# Omega2-IO-Power.net
KiCad netlist of a schematic drawn in EAGLE
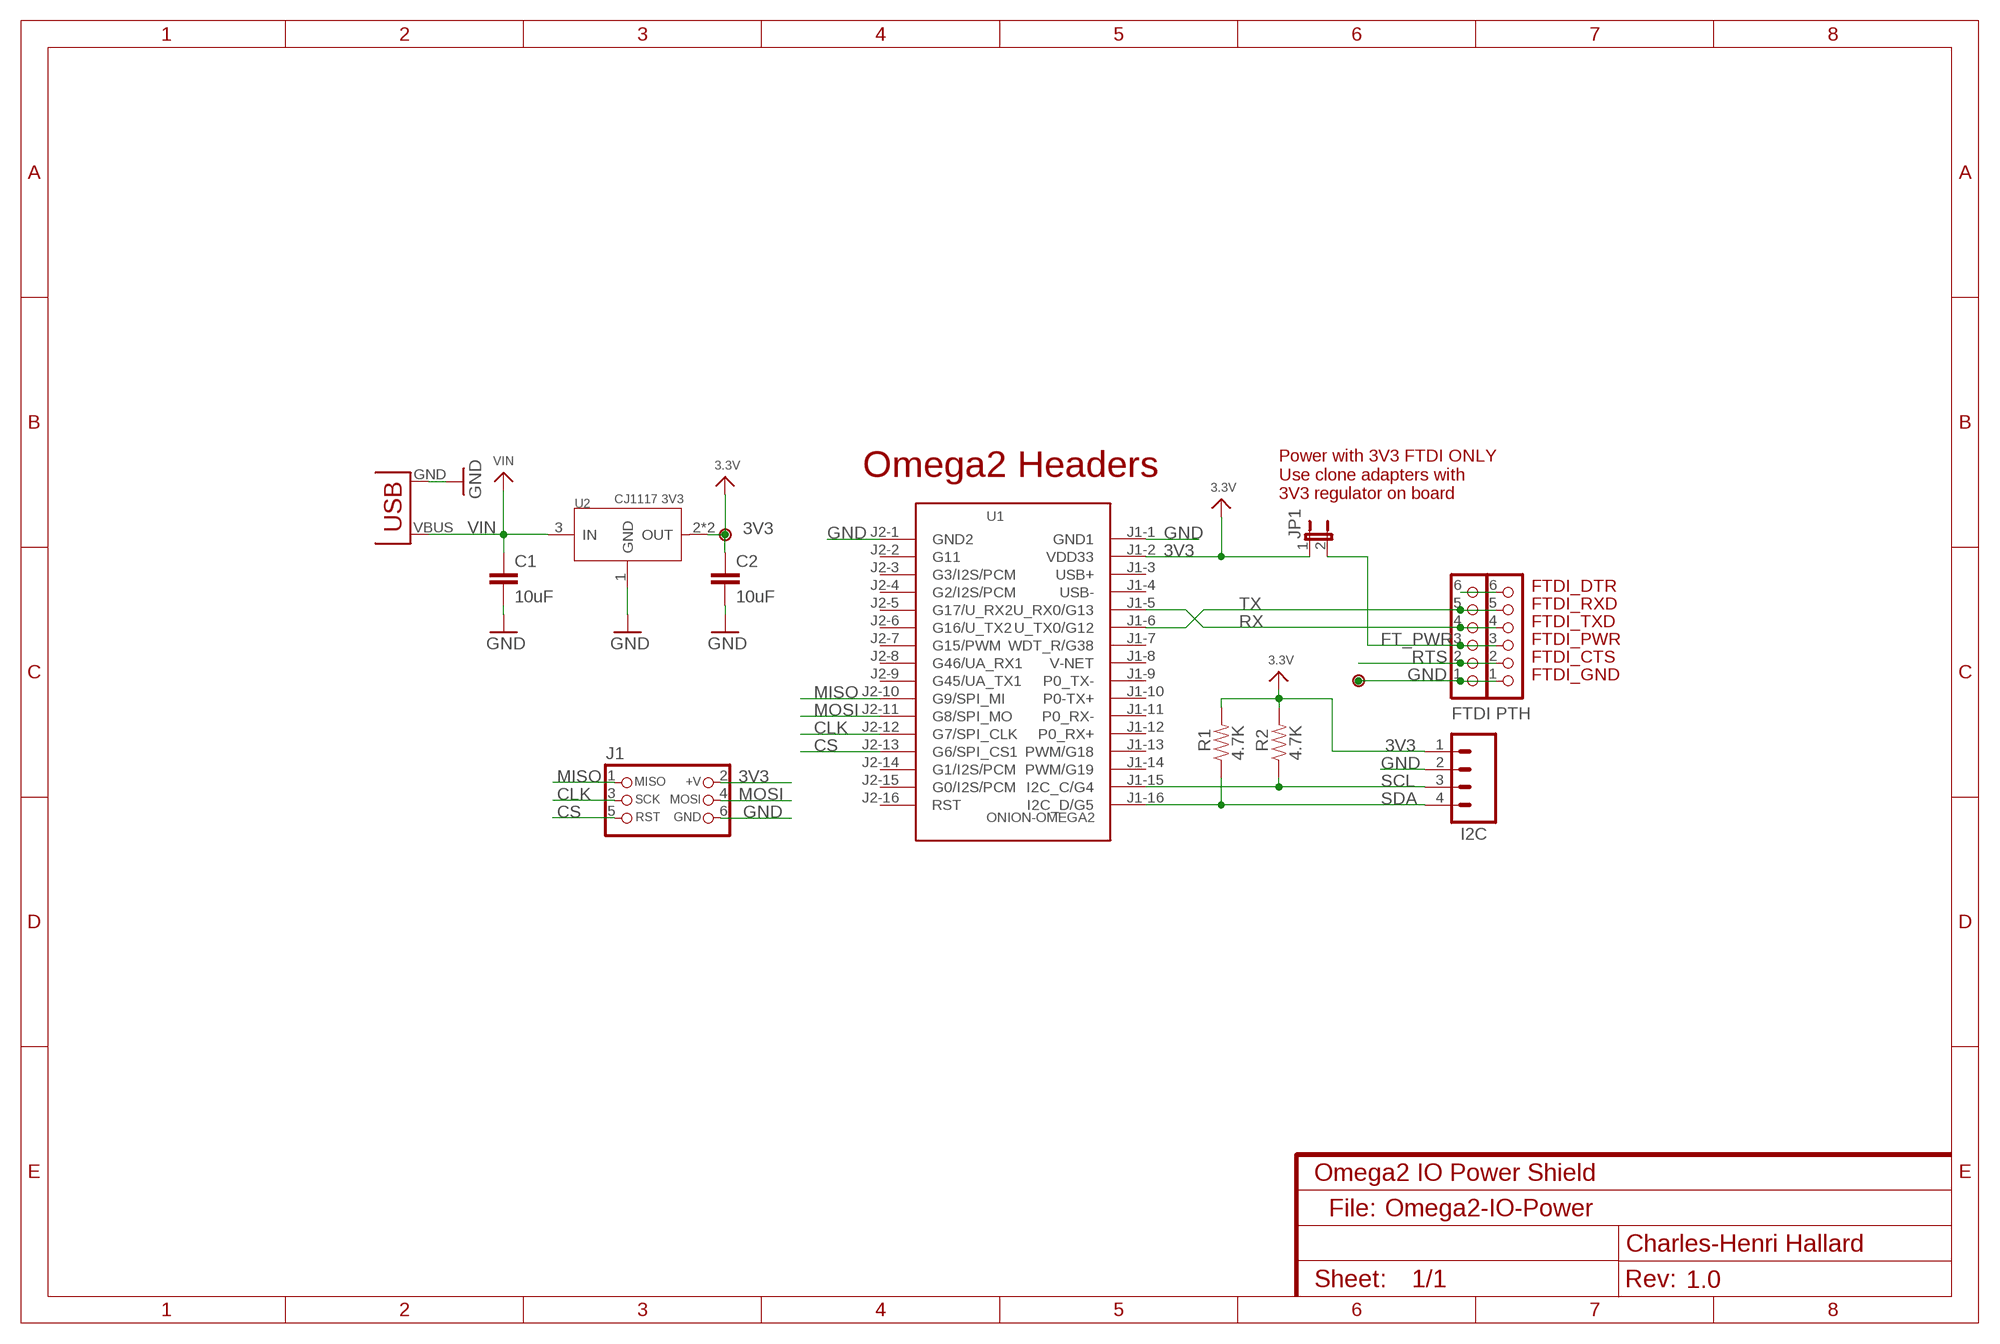
[diagram p0: schematic, sheet 1]

(export (version "E")
  (design (tool "Eeschema 10.0.6"))
  (components
    (comp (ref "C1")
      (value "10uF")
      (footprint "eagle-import:0805-CAP-LARGEPADS")
      (libsource (lib "eagle-import") (part "CAP0805-CAP-LARGEPADS"))
    )
    (comp (ref "C2")
      (value "10uF")
      (footprint "eagle-import:0805-CAP-LARGEPADS")
      (libsource (lib "eagle-import") (part "CAP0805-CAP-LARGEPADS"))
    )
    (comp (ref "FTDI")
      (value "CON_HEADER_1X06-PTH")
      (footprint "eagle-import:M1X6")
      (libsource (lib "eagle-import") (part "CON_HEADER_1X06-PTH"))
    )
    (comp (ref "I2C")
      (value "M04PTH")
      (footprint "eagle-import:1X04")
      (libsource (lib "eagle-import") (part "M04PTH"))
    )
    (comp (ref "J1")
      (value "CON_HEADER_PRG_AVR_ICSP-PTH")
      (footprint "eagle-import:HEADER_PRG_2X03")
      (libsource (lib "eagle-import") (part "CON_HEADER_PRG_AVR_ICSP-PTH"))
    )
    (comp (ref "JP1")
      (value "JUMPER2")
      (footprint "eagle-import:JUMPER2")
      (libsource (lib "eagle-import") (part "JUMPER2"))
    )
    (comp (ref "P1")
      (value "PADNORMAL")
      (footprint "eagle-import:PAD")
      (libsource (lib "eagle-import") (part "PADNORMAL"))
    )
    (comp (ref "P2")
      (value "PADNORMAL")
      (footprint "eagle-import:PAD")
      (libsource (lib "eagle-import") (part "PADNORMAL"))
    )
    (comp (ref "PTH")
      (value "CON_HEADER_1X06")
      (footprint "eagle-import:M1X6_MALE_RIGHT_ANGLED_SMD_NO_HOLES")
      (libsource (lib "eagle-import") (part "CON_HEADER_1X06"))
    )
    (comp (ref "R1")
      (value "4.7K")
      (footprint "eagle-import:0805-RES")
      (libsource (lib "eagle-import") (part "RESISTOR0805-RES"))
    )
    (comp (ref "R2")
      (value "4.7K")
      (footprint "eagle-import:0805-RES")
      (libsource (lib "eagle-import") (part "RESISTOR0805-RES"))
    )
    (comp (ref "U1")
      (value "ONION-OMEGA2")
      (footprint "eagle-import:ONION-2MM-2X16")
      (libsource (lib "eagle-import") (part "ONION-OMEGA2"))
    )
    (comp (ref "U2")
      (value "CJ1117 3V3")
      (footprint "eagle-import:SOT89")
      (libsource (lib "eagle-import") (part "CJ1117-3.3-1310120P1"))
    )
    (comp (ref "USB")
      (value "USB_POWER")
      (footprint "eagle-import:USB_MINIB_POWER")
      (libsource (lib "eagle-import") (part "USB_POWER"))
    )
  )
  (nets
    (net (code "1") (name "/CLK") (class "Default")
      (node (ref "J1") (pin "3") (pinfunction "SCK_3") (pintype "passive"))
      (node (ref "U1") (pin "J2-12") (pinfunction "G7/SPI_CLK_J2-12") (pintype "bidirectional"))
    )
    (net (code "2") (name "/CS") (class "Default")
      (node (ref "J1") (pin "5") (pinfunction "RST_5") (pintype "passive"))
      (node (ref "U1") (pin "J2-13") (pinfunction "G6/SPI_CS1_J2-13") (pintype "bidirectional"))
    )
    (net (code "3") (name "/FT_PWR") (class "Default")
      (node (ref "FTDI") (pin "3") (pinfunction "3_3") (pintype "passive"))
      (node (ref "JP1") (pin "2") (pinfunction "2_2") (pintype "passive"))
      (node (ref "PTH") (pin "3") (pinfunction "3_3") (pintype "passive"))
    )
    (net (code "4") (name "/MISO") (class "Default")
      (node (ref "J1") (pin "1") (pinfunction "MISO_1") (pintype "passive"))
      (node (ref "U1") (pin "J2-10") (pinfunction "G9/SPI_MI_J2-10") (pintype "bidirectional"))
    )
    (net (code "5") (name "/MOSI") (class "Default")
      (node (ref "J1") (pin "4") (pinfunction "MOSI_4") (pintype "passive"))
      (node (ref "U1") (pin "J2-11") (pinfunction "G8/SPI_MO_J2-11") (pintype "bidirectional"))
    )
    (net (code "6") (name "/RTS") (class "Default")
      (node (ref "FTDI") (pin "2") (pinfunction "2_2") (pintype "bidirectional"))
      (node (ref "PTH") (pin "2") (pinfunction "2_2") (pintype "bidirectional"))
    )
    (net (code "7") (name "/RX") (class "Default")
      (node (ref "FTDI") (pin "4") (pinfunction "4_4") (pintype "passive"))
      (node (ref "PTH") (pin "4") (pinfunction "4_4") (pintype "passive"))
      (node (ref "U1") (pin "J1-5") (pinfunction "U_RX0/G13_J1-5") (pintype "bidirectional"))
    )
    (net (code "8") (name "/SCL") (class "Default")
      (node (ref "I2C") (pin "3") (pinfunction "3_3") (pintype "passive"))
      (node (ref "R2") (pin "1") (pinfunction "1_1") (pintype "passive"))
      (node (ref "U1") (pin "J1-15") (pinfunction "I2C_C/G4_J1-15") (pintype "bidirectional"))
    )
    (net (code "9") (name "/SDA") (class "Default")
      (node (ref "I2C") (pin "4") (pinfunction "4_4") (pintype "passive"))
      (node (ref "R1") (pin "1") (pinfunction "1_1") (pintype "passive"))
      (node (ref "U1") (pin "J1-16") (pinfunction "I2C_D/G5_J1-16") (pintype "bidirectional"))
    )
    (net (code "10") (name "/TX") (class "Default")
      (node (ref "FTDI") (pin "5") (pinfunction "5_5") (pintype "passive"))
      (node (ref "PTH") (pin "5") (pinfunction "5_5") (pintype "passive"))
      (node (ref "U1") (pin "J1-6") (pinfunction "U_TX0/G12_J1-6") (pintype "bidirectional"))
    )
    (net (code "11") (name "3.3V") (class "Default")
      (node (ref "C2") (pin "1") (pinfunction "1_1") (pintype "passive"))
      (node (ref "I2C") (pin "1") (pinfunction "1_1") (pintype "passive"))
      (node (ref "J1") (pin "2") (pinfunction "+V_2") (pintype "passive"))
      (node (ref "JP1") (pin "1") (pinfunction "1_1") (pintype "passive"))
      (node (ref "P1") (pin "1") (pinfunction "1_1") (pintype "bidirectional"))
      (node (ref "R1") (pin "2") (pinfunction "2_2") (pintype "passive"))
      (node (ref "R2") (pin "2") (pinfunction "2_2") (pintype "passive"))
      (node (ref "U1") (pin "J1-2") (pinfunction "VDD33_J1-2") (pintype "bidirectional"))
      (node (ref "U2") (pin "2") (pinfunction "OUT_2") (pintype "bidirectional"))
      (node (ref "U2") (pin "4") (pinfunction "OUT_4") (pintype "bidirectional"))
    )
    (net (code "12") (name "GND") (class "Default")
      (node (ref "C1") (pin "2") (pinfunction "2_2") (pintype "passive"))
      (node (ref "C2") (pin "2") (pinfunction "2_2") (pintype "passive"))
      (node (ref "FTDI") (pin "1") (pinfunction "1_1") (pintype "bidirectional"))
      (node (ref "I2C") (pin "2") (pinfunction "2_2") (pintype "passive"))
      (node (ref "J1") (pin "6") (pinfunction "GND_6") (pintype "passive"))
      (node (ref "P2") (pin "1") (pinfunction "1_1") (pintype "bidirectional"))
      (node (ref "PTH") (pin "1") (pinfunction "1_1") (pintype "bidirectional"))
      (node (ref "U1") (pin "J1-1") (pinfunction "GND1_J1-1") (pintype "bidirectional"))
      (node (ref "U1") (pin "J2-1") (pinfunction "GND2_J2-1") (pintype "bidirectional"))
      (node (ref "U2") (pin "1") (pinfunction "GND_1") (pintype "bidirectional"))
      (node (ref "USB") (pin "GND") (pinfunction "GND_GND") (pintype "bidirectional"))
    )
    (net (code "13") (name "Net-(FTDI-Pad6)") (class "Default")
      (node (ref "FTDI") (pin "6") (pinfunction "6_6") (pintype "passive"))
      (node (ref "PTH") (pin "6") (pinfunction "6_6") (pintype "passive"))
    )
    (net (code "14") (name "VIN") (class "Default")
      (node (ref "C1") (pin "1") (pinfunction "1_1") (pintype "passive"))
      (node (ref "U2") (pin "3") (pinfunction "IN_3") (pintype "bidirectional"))
      (node (ref "USB") (pin "VBUS") (pinfunction "VCC_VBUS") (pintype "bidirectional"))
    )
    (net (code "15") (name "unconnected-(U1-G0{slash}I2S{slash}PCM-PadJ2-15)") (class "Default")
      (node (ref "U1") (pin "J2-15") (pinfunction "G0/I2S/PCM_J2-15") (pintype "bidirectional"))
    )
    (net (code "16") (name "unconnected-(U1-G1{slash}I2S{slash}PCM-PadJ2-14)") (class "Default")
      (node (ref "U1") (pin "J2-14") (pinfunction "G1/I2S/PCM_J2-14") (pintype "bidirectional"))
    )
    (net (code "17") (name "unconnected-(U1-G2{slash}I2S{slash}PCM-PadJ2-4)") (class "Default")
      (node (ref "U1") (pin "J2-4") (pinfunction "G2/I2S/PCM_J2-4") (pintype "bidirectional"))
    )
    (net (code "18") (name "unconnected-(U1-G3{slash}I2S{slash}PCM-PadJ2-3)") (class "Default")
      (node (ref "U1") (pin "J2-3") (pinfunction "G3/I2S/PCM_J2-3") (pintype "bidirectional"))
    )
    (net (code "19") (name "unconnected-(U1-G11-PadJ2-2)") (class "Default")
      (node (ref "U1") (pin "J2-2") (pinfunction "G11_J2-2") (pintype "bidirectional"))
    )
    (net (code "20") (name "unconnected-(U1-G15{slash}PWM-PadJ2-7)") (class "Default")
      (node (ref "U1") (pin "J2-7") (pinfunction "G15/PWM_J2-7") (pintype "bidirectional"))
    )
    (net (code "21") (name "unconnected-(U1-G16{slash}U_TX2-PadJ2-6)") (class "Default")
      (node (ref "U1") (pin "J2-6") (pinfunction "G16/U_TX2_J2-6") (pintype "bidirectional"))
    )
    (net (code "22") (name "unconnected-(U1-G17{slash}U_RX2-PadJ2-5)") (class "Default")
      (node (ref "U1") (pin "J2-5") (pinfunction "G17/U_RX2_J2-5") (pintype "bidirectional"))
    )
    (net (code "23") (name "unconnected-(U1-G45{slash}UA_TX1-PadJ2-9)") (class "Default")
      (node (ref "U1") (pin "J2-9") (pinfunction "G45/UA_TX1_J2-9") (pintype "bidirectional"))
    )
    (net (code "24") (name "unconnected-(U1-G46{slash}UA_RX1-PadJ2-8)") (class "Default")
      (node (ref "U1") (pin "J2-8") (pinfunction "G46/UA_RX1_J2-8") (pintype "bidirectional"))
    )
    (net (code "25") (name "unconnected-(U1-P0-TX+-PadJ1-10)") (class "Default")
      (node (ref "U1") (pin "J1-10") (pinfunction "P0-TX+_J1-10") (pintype "bidirectional"))
    )
    (net (code "26") (name "unconnected-(U1-P0_RX+-PadJ1-12)") (class "Default")
      (node (ref "U1") (pin "J1-12") (pinfunction "P0_RX+_J1-12") (pintype "bidirectional"))
    )
    (net (code "27") (name "unconnected-(U1-P0_RX--PadJ1-11)") (class "Default")
      (node (ref "U1") (pin "J1-11") (pinfunction "P0_RX-_J1-11") (pintype "bidirectional"))
    )
    (net (code "28") (name "unconnected-(U1-P0_TX--PadJ1-9)") (class "Default")
      (node (ref "U1") (pin "J1-9") (pinfunction "P0_TX-_J1-9") (pintype "bidirectional"))
    )
    (net (code "29") (name "unconnected-(U1-PWM{slash}G18-PadJ1-13)") (class "Default")
      (node (ref "U1") (pin "J1-13") (pinfunction "PWM/G18_J1-13") (pintype "bidirectional"))
    )
    (net (code "30") (name "unconnected-(U1-PWM{slash}G19-PadJ1-14)") (class "Default")
      (node (ref "U1") (pin "J1-14") (pinfunction "PWM/G19_J1-14") (pintype "bidirectional"))
    )
    (net (code "31") (name "unconnected-(U1-RST-PadJ2-16)") (class "Default")
      (node (ref "U1") (pin "J2-16") (pinfunction "RST_J2-16") (pintype "bidirectional"))
    )
    (net (code "32") (name "unconnected-(U1-USB+-PadJ1-3)") (class "Default")
      (node (ref "U1") (pin "J1-3") (pinfunction "USB+_J1-3") (pintype "bidirectional"))
    )
    (net (code "33") (name "unconnected-(U1-USB--PadJ1-4)") (class "Default")
      (node (ref "U1") (pin "J1-4") (pinfunction "USB-_J1-4") (pintype "bidirectional"))
    )
    (net (code "34") (name "unconnected-(U1-V-NET-PadJ1-8)") (class "Default")
      (node (ref "U1") (pin "J1-8") (pinfunction "V-NET_J1-8") (pintype "bidirectional"))
    )
    (net (code "35") (name "unconnected-(U1-WDT_R{slash}G38-PadJ1-7)") (class "Default")
      (node (ref "U1") (pin "J1-7") (pinfunction "WDT_R/G38_J1-7") (pintype "bidirectional"))
    )
  )
)
